# ArbotixPro-JTAGProg.net
KiCad netlist of a schematic drawn in EAGLE
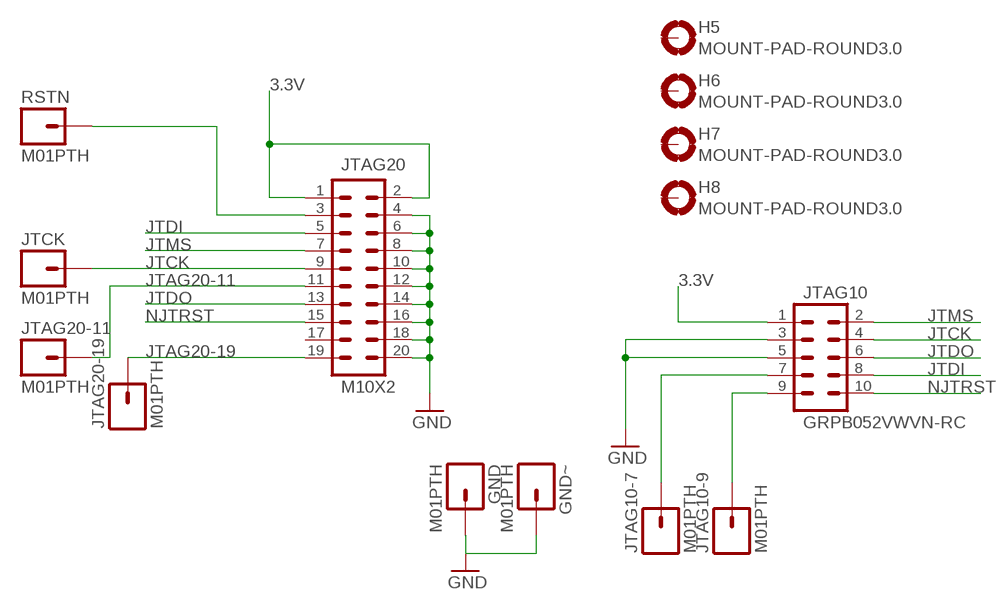
[diagram p0: schematic, sheet 1]

(export (version "E")
  (design (tool "Eeschema 10.0.6"))
  (components
    (comp (ref "GND")
      (value "M01PTH")
      (footprint "eagle-import:1X01")
      (libsource (lib "eagle-import") (part "M01PTH"))
    )
    (comp (ref "GND~")
      (value "M01PTH")
      (footprint "eagle-import:1X01")
      (libsource (lib "eagle-import") (part "M01PTH"))
    )
    (comp (ref "H5")
      (value "MOUNT-PAD-ROUND3.0")
      (footprint "eagle-import:3,0-PAD")
      (libsource (lib "eagle-import") (part "MOUNT-PAD-ROUND3.0"))
    )
    (comp (ref "H6")
      (value "MOUNT-PAD-ROUND3.0")
      (footprint "eagle-import:3,0-PAD")
      (libsource (lib "eagle-import") (part "MOUNT-PAD-ROUND3.0"))
    )
    (comp (ref "H7")
      (value "MOUNT-PAD-ROUND3.0")
      (footprint "eagle-import:3,0-PAD")
      (libsource (lib "eagle-import") (part "MOUNT-PAD-ROUND3.0"))
    )
    (comp (ref "H8")
      (value "MOUNT-PAD-ROUND3.0")
      (footprint "eagle-import:3,0-PAD")
      (libsource (lib "eagle-import") (part "MOUNT-PAD-ROUND3.0"))
    )
    (comp (ref "JTAG10")
      (value "GRPB052VWVN-RC")
      (footprint "eagle-import:2X5_PTH_SILK_.05")
      (libsource (lib "eagle-import") (part "M05X20.05_IN_PTH_SILK"))
    )
    (comp (ref "JTAG10-7")
      (value "M01PTH")
      (footprint "eagle-import:1X01")
      (libsource (lib "eagle-import") (part "M01PTH"))
    )
    (comp (ref "JTAG10-9")
      (value "M01PTH")
      (footprint "eagle-import:1X01")
      (libsource (lib "eagle-import") (part "M01PTH"))
    )
    (comp (ref "JTAG20")
      (value "M10X2")
      (footprint "eagle-import:2X10")
      (libsource (lib "eagle-import") (part "M10X2"))
    )
    (comp (ref "JTAG20-11")
      (value "M01PTH")
      (footprint "eagle-import:1X01")
      (libsource (lib "eagle-import") (part "M01PTH"))
    )
    (comp (ref "JTAG20-19")
      (value "M01PTH")
      (footprint "eagle-import:1X01")
      (libsource (lib "eagle-import") (part "M01PTH"))
    )
    (comp (ref "JTCK")
      (value "M01PTH")
      (footprint "eagle-import:1X01")
      (libsource (lib "eagle-import") (part "M01PTH"))
    )
    (comp (ref "RSTN")
      (value "M01PTH")
      (footprint "eagle-import:1X01")
      (libsource (lib "eagle-import") (part "M01PTH"))
    )
  )
  (nets
    (net (code "1") (name "/3.3V") (class "Default")
      (node (ref "JTAG10") (pin "1") (pinfunction "1_1") (pintype "passive"))
      (node (ref "JTAG20") (pin "1") (pinfunction "1_1") (pintype "passive"))
      (node (ref "JTAG20") (pin "2") (pinfunction "2_2") (pintype "passive"))
    )
    (net (code "2") (name "/JTAG20-11") (class "Default")
      (node (ref "JTAG20") (pin "11") (pinfunction "11_11") (pintype "passive"))
      (node (ref "JTAG20-11") (pin "1") (pinfunction "1_1") (pintype "passive"))
    )
    (net (code "3") (name "/JTAG20-19") (class "Default")
      (node (ref "JTAG20") (pin "19") (pinfunction "19_19") (pintype "passive"))
      (node (ref "JTAG20-19") (pin "1") (pinfunction "1_1") (pintype "passive"))
    )
    (net (code "4") (name "/JTCK") (class "Default")
      (node (ref "JTAG10") (pin "4") (pinfunction "4_4") (pintype "passive"))
      (node (ref "JTAG20") (pin "9") (pinfunction "9_9") (pintype "passive"))
      (node (ref "JTCK") (pin "1") (pinfunction "1_1") (pintype "passive"))
    )
    (net (code "5") (name "/JTDI") (class "Default")
      (node (ref "JTAG10") (pin "8") (pinfunction "8_8") (pintype "passive"))
      (node (ref "JTAG20") (pin "5") (pinfunction "5_5") (pintype "passive"))
    )
    (net (code "6") (name "/JTDO") (class "Default")
      (node (ref "JTAG10") (pin "6") (pinfunction "6_6") (pintype "passive"))
      (node (ref "JTAG20") (pin "13") (pinfunction "13_13") (pintype "passive"))
    )
    (net (code "7") (name "/JTMS") (class "Default")
      (node (ref "JTAG10") (pin "2") (pinfunction "2_2") (pintype "passive"))
      (node (ref "JTAG20") (pin "7") (pinfunction "7_7") (pintype "passive"))
    )
    (net (code "8") (name "/NJTRST") (class "Default")
      (node (ref "JTAG10") (pin "10") (pinfunction "10_10") (pintype "passive"))
      (node (ref "JTAG20") (pin "15") (pinfunction "15_15") (pintype "passive"))
    )
    (net (code "9") (name "GND") (class "Default")
      (node (ref "GND") (pin "1") (pinfunction "1_1") (pintype "passive"))
      (node (ref "GND~") (pin "1") (pinfunction "1_1") (pintype "passive"))
      (node (ref "JTAG10") (pin "3") (pinfunction "3_3") (pintype "passive"))
      (node (ref "JTAG10") (pin "5") (pinfunction "5_5") (pintype "passive"))
      (node (ref "JTAG20") (pin "10") (pinfunction "10_10") (pintype "passive"))
      (node (ref "JTAG20") (pin "12") (pinfunction "12_12") (pintype "passive"))
      (node (ref "JTAG20") (pin "14") (pinfunction "14_14") (pintype "passive"))
      (node (ref "JTAG20") (pin "16") (pinfunction "16_16") (pintype "passive"))
      (node (ref "JTAG20") (pin "18") (pinfunction "18_18") (pintype "passive"))
      (node (ref "JTAG20") (pin "20") (pinfunction "20_20") (pintype "passive"))
      (node (ref "JTAG20") (pin "4") (pinfunction "4_4") (pintype "passive"))
      (node (ref "JTAG20") (pin "6") (pinfunction "6_6") (pintype "passive"))
      (node (ref "JTAG20") (pin "8") (pinfunction "8_8") (pintype "passive"))
    )
    (net (code "10") (name "Net-(JTAG10-7-Pad1)") (class "Default")
      (node (ref "JTAG10") (pin "7") (pinfunction "7_7") (pintype "passive"))
      (node (ref "JTAG10-7") (pin "1") (pinfunction "1_1") (pintype "passive"))
    )
    (net (code "11") (name "Net-(JTAG10-9-Pad1)") (class "Default")
      (node (ref "JTAG10") (pin "9") (pinfunction "9_9") (pintype "passive"))
      (node (ref "JTAG10-9") (pin "1") (pinfunction "1_1") (pintype "passive"))
    )
    (net (code "12") (name "Net-(JTAG20-Pad3)") (class "Default")
      (node (ref "JTAG20") (pin "3") (pinfunction "3_3") (pintype "passive"))
      (node (ref "RSTN") (pin "1") (pinfunction "1_1") (pintype "passive"))
    )
    (net (code "13") (name "unconnected-(H5-MOUNT-PadB3,0)") (class "Default")
      (node (ref "H5") (pin "B3,0") (pinfunction "MOUNT_B3,0") (pintype "passive"))
    )
    (net (code "14") (name "unconnected-(H6-MOUNT-PadB3,0)") (class "Default")
      (node (ref "H6") (pin "B3,0") (pinfunction "MOUNT_B3,0") (pintype "passive"))
    )
    (net (code "15") (name "unconnected-(H7-MOUNT-PadB3,0)") (class "Default")
      (node (ref "H7") (pin "B3,0") (pinfunction "MOUNT_B3,0") (pintype "passive"))
    )
    (net (code "16") (name "unconnected-(H8-MOUNT-PadB3,0)") (class "Default")
      (node (ref "H8") (pin "B3,0") (pinfunction "MOUNT_B3,0") (pintype "passive"))
    )
    (net (code "17") (name "unconnected-(JTAG20-Pad17)") (class "Default")
      (node (ref "JTAG20") (pin "17") (pinfunction "17_17") (pintype "passive"))
    )
  )
)
